# Sheet1.net
KiCad netlist of a schematic drawn in Altium Designer
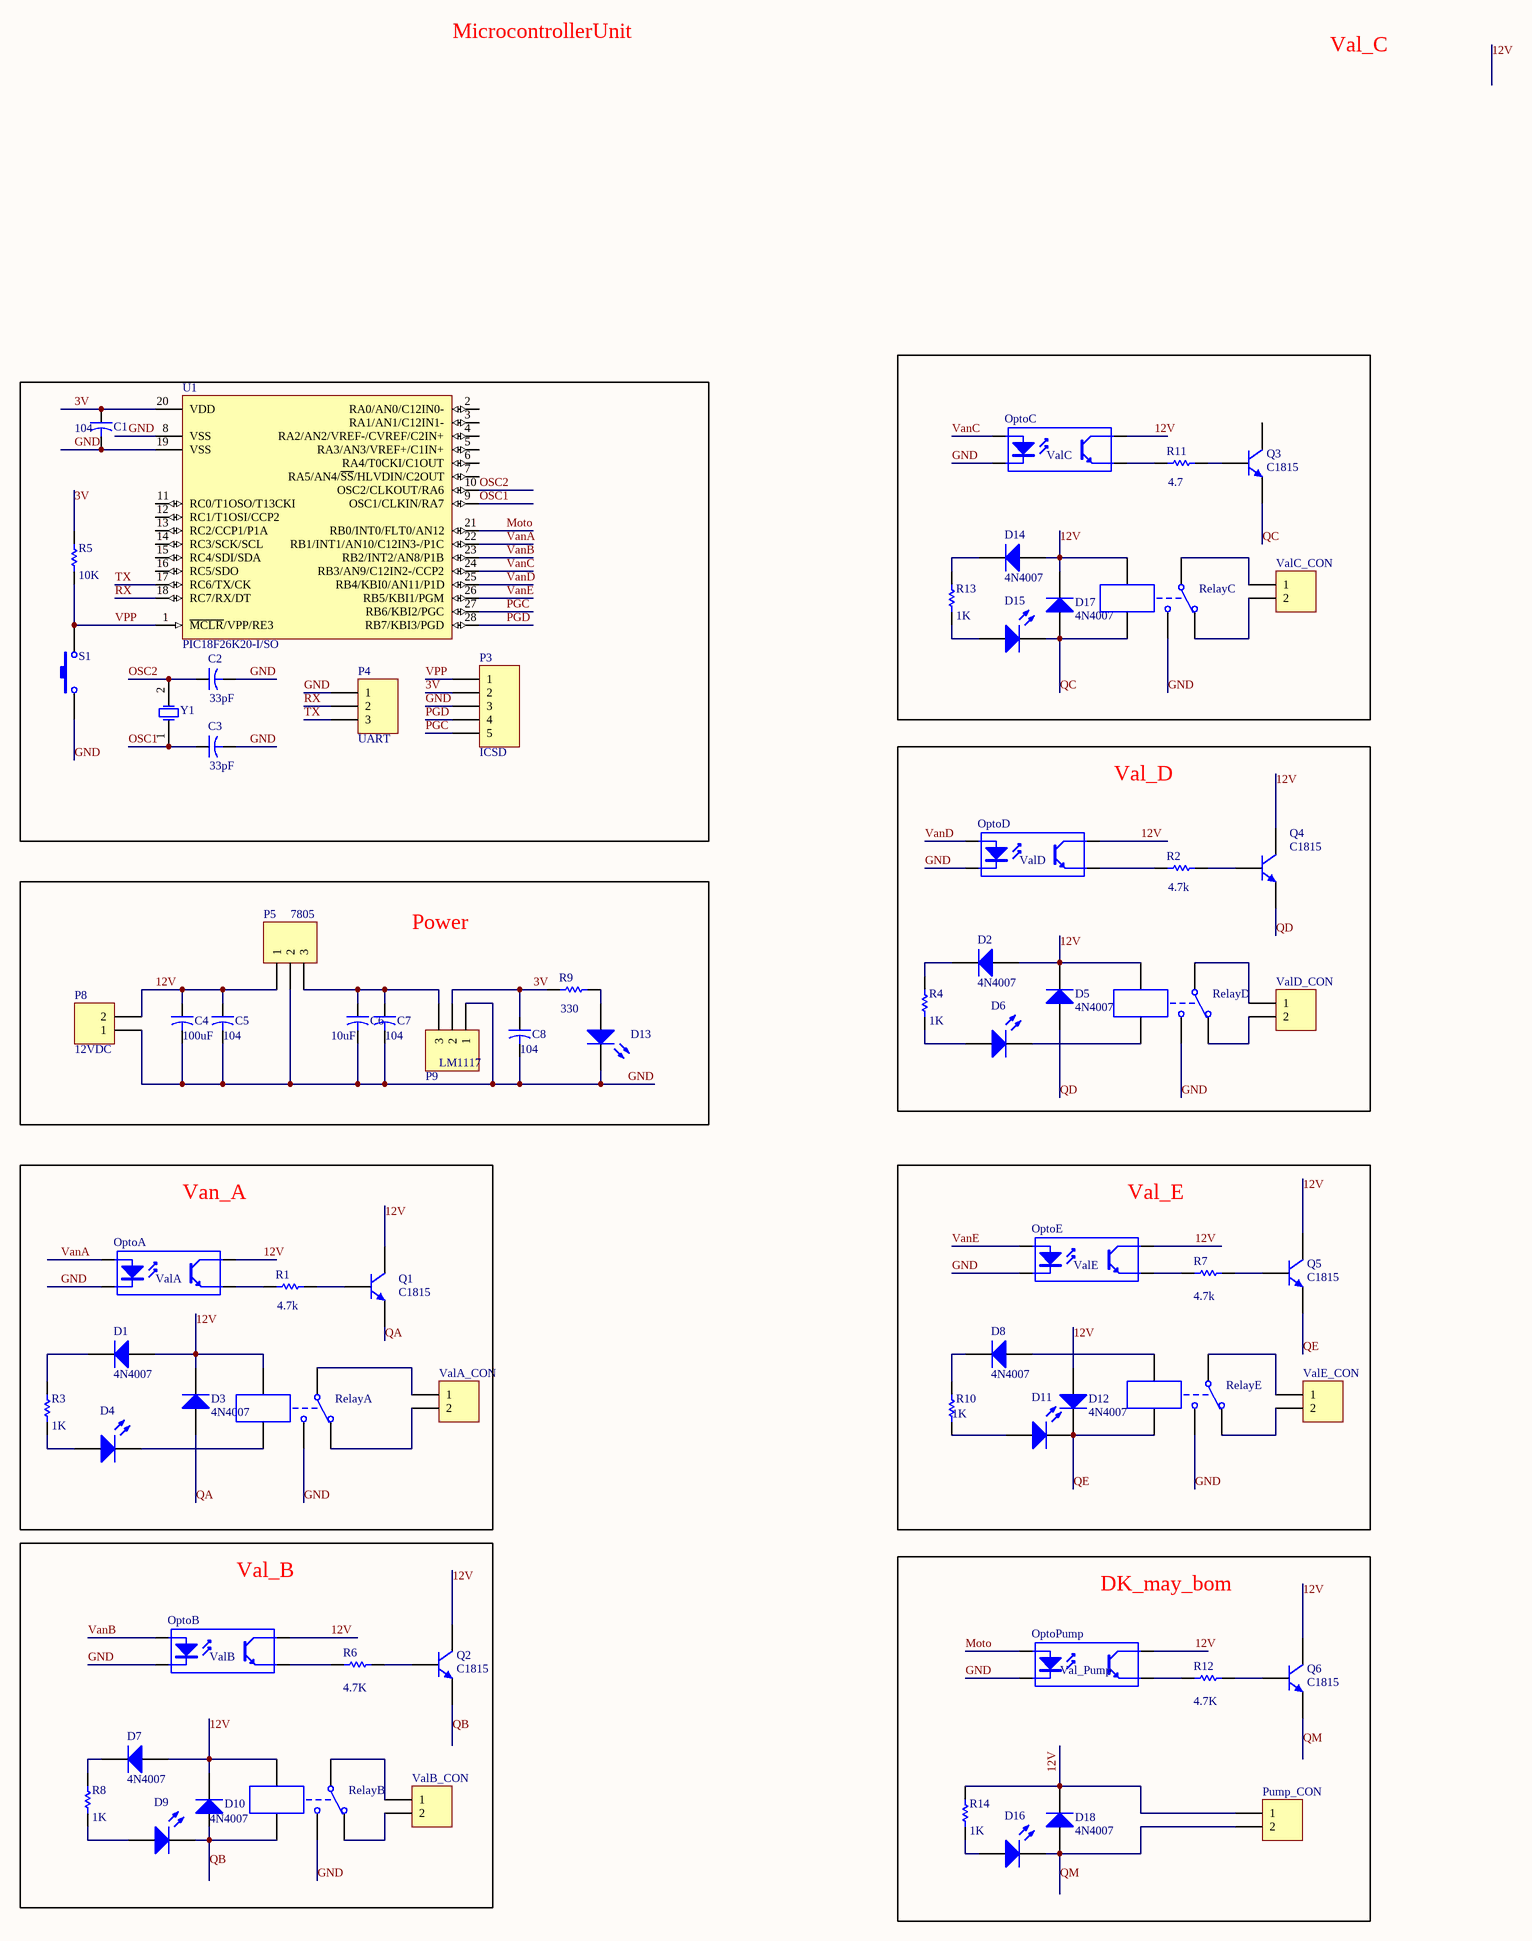
[diagram p0: Sheet1.SchDoc]

(export (version "E")
  (design (tool "Eeschema 10.0.6"))
  (components
    (comp (ref "C1")
      (value "104")
      (footprint "CN1")
      (description "Capacitor")
      (fields (field (name "Comment") "Cap2") (field (name "PUBLISHER") "Altium Limited"))
      (libsource (lib "Miscellaneous Devices") (part "Cap2"))
    )
    (comp (ref "C2")
      (value "33pF")
      (footprint "CN1")
      (description "Capacitor")
      (fields (field (name "Comment") "Cap2") (field (name "PUBLISHER") "Altium Limited"))
      (libsource (lib "Miscellaneous Devices") (part "Cap2"))
    )
    (comp (ref "C3")
      (value "33pF")
      (footprint "CN1")
      (description "Capacitor")
      (fields (field (name "Comment") "Cap2") (field (name "PUBLISHER") "Altium Limited"))
      (libsource (lib "Miscellaneous Devices") (part "Cap2"))
    )
    (comp (ref "C4")
      (value "100uF")
      (footprint "CP1.5/2.5")
      (description "Capacitor")
      (fields (field (name "Comment") "Cap2") (field (name "PUBLISHER") "Altium Limited"))
      (libsource (lib "Miscellaneous Devices") (part "Cap2"))
    )
    (comp (ref "C5")
      (value "104")
      (footprint "CN1")
      (description "Capacitor")
      (fields (field (name "Comment") "Cap2") (field (name "PUBLISHER") "Altium Limited"))
      (libsource (lib "Miscellaneous Devices") (part "Cap2"))
    )
    (comp (ref "C6")
      (value "10uF")
      (footprint "CP1/2")
      (description "Capacitor")
      (fields (field (name "Comment") "Cap2") (field (name "PUBLISHER") "Altium Limited"))
      (libsource (lib "Miscellaneous Devices") (part "Cap2"))
    )
    (comp (ref "C7")
      (value "104")
      (footprint "CN1")
      (description "Capacitor")
      (fields (field (name "Comment") "Cap2") (field (name "PUBLISHER") "Altium Limited"))
      (libsource (lib "Miscellaneous Devices") (part "Cap2"))
    )
    (comp (ref "C8")
      (value "104")
      (footprint "CN1")
      (description "Capacitor")
      (fields (field (name "Comment") "Cap2") (field (name "PUBLISHER") "Altium Limited"))
      (libsource (lib "Miscellaneous Devices") (part "Cap2"))
    )
    (comp (ref "D1")
      (value "4N4007")
      (footprint "D2A")
      (description "1 Amp General Purpose Rectifier")
      (fields (field (name "PUBLISHER") "Altium Limited"))
      (libsource (lib "Miscellaneous Devices") (part "Diode 1N4007"))
    )
    (comp (ref "D2")
      (value "4N4007")
      (footprint "D2A")
      (description "1 Amp General Purpose Rectifier")
      (fields (field (name "PUBLISHER") "Altium Limited"))
      (libsource (lib "Miscellaneous Devices") (part "Diode 1N4007"))
    )
    (comp (ref "D3")
      (value "4N4007")
      (footprint "D2A")
      (description "1 Amp General Purpose Rectifier")
      (fields (field (name "PUBLISHER") "Altium Limited"))
      (libsource (lib "Miscellaneous Devices") (part "Diode 1N4007"))
    )
    (comp (ref "D4")
      (value "LED1")
      (footprint "LED-5TRED")
      (description "Typical RED GaAs LED")
      (fields (field (name "PUBLISHER") "Altium Limited"))
      (libsource (lib "Miscellaneous Devices") (part "LED1"))
    )
    (comp (ref "D5")
      (value "4N4007")
      (footprint "D2A")
      (description "1 Amp General Purpose Rectifier")
      (fields (field (name "PUBLISHER") "Altium Limited"))
      (libsource (lib "Miscellaneous Devices") (part "Diode 1N4007"))
    )
    (comp (ref "D6")
      (value "LED1")
      (footprint "LED-5TRED")
      (description "Typical RED GaAs LED")
      (fields (field (name "PUBLISHER") "Altium Limited"))
      (libsource (lib "Miscellaneous Devices") (part "LED1"))
    )
    (comp (ref "D7")
      (value "4N4007")
      (footprint "D2A")
      (description "1 Amp General Purpose Rectifier")
      (fields (field (name "PUBLISHER") "Altium Limited"))
      (libsource (lib "Miscellaneous Devices") (part "Diode 1N4007"))
    )
    (comp (ref "D8")
      (value "4N4007")
      (footprint "D2A")
      (description "1 Amp General Purpose Rectifier")
      (fields (field (name "PUBLISHER") "Altium Limited"))
      (libsource (lib "Miscellaneous Devices") (part "Diode 1N4007"))
    )
    (comp (ref "D9")
      (value "LED1")
      (footprint "LED-5TRED")
      (description "Typical RED GaAs LED")
      (fields (field (name "PUBLISHER") "Altium Limited"))
      (libsource (lib "Miscellaneous Devices") (part "LED1"))
    )
    (comp (ref "D10")
      (value "4N4007")
      (footprint "D2A")
      (description "1 Amp General Purpose Rectifier")
      (fields (field (name "PUBLISHER") "Altium Limited"))
      (libsource (lib "Miscellaneous Devices") (part "Diode 1N4007"))
    )
    (comp (ref "D11")
      (value "LED1")
      (footprint "LED-5TRED")
      (description "Typical RED GaAs LED")
      (fields (field (name "PUBLISHER") "Altium Limited"))
      (libsource (lib "Miscellaneous Devices") (part "LED1"))
    )
    (comp (ref "D12")
      (value "4N4007")
      (footprint "D2A")
      (description "1 Amp General Purpose Rectifier")
      (fields (field (name "PUBLISHER") "Altium Limited"))
      (libsource (lib "Miscellaneous Devices") (part "Diode 1N4007"))
    )
    (comp (ref "D13")
      (value "LED1")
      (footprint "LED-5TRED")
      (description "Typical RED GaAs LED")
      (fields (field (name "PUBLISHER") "Altium Limited"))
      (libsource (lib "Miscellaneous Devices") (part "LED1"))
    )
    (comp (ref "D14")
      (value "4N4007")
      (footprint "D2A")
      (description "1 Amp General Purpose Rectifier")
      (fields (field (name "PUBLISHER") "Altium Limited"))
      (libsource (lib "Miscellaneous Devices") (part "Diode 1N4007"))
    )
    (comp (ref "D15")
      (value "LED1")
      (footprint "LED-5TRED")
      (description "Typical RED GaAs LED")
      (fields (field (name "PUBLISHER") "Altium Limited"))
      (libsource (lib "Miscellaneous Devices") (part "LED1"))
    )
    (comp (ref "D16")
      (value "LED1")
      (footprint "LED-5TRED")
      (description "Typical RED GaAs LED")
      (fields (field (name "PUBLISHER") "Altium Limited"))
      (libsource (lib "Miscellaneous Devices") (part "LED1"))
    )
    (comp (ref "D17")
      (value "4N4007")
      (footprint "D2A")
      (description "1 Amp General Purpose Rectifier")
      (fields (field (name "PUBLISHER") "Altium Limited"))
      (libsource (lib "Miscellaneous Devices") (part "Diode 1N4007"))
    )
    (comp (ref "D18")
      (value "4N4007")
      (footprint "D2A")
      (description "1 Amp General Purpose Rectifier")
      (fields (field (name "PUBLISHER") "Altium Limited"))
      (libsource (lib "Miscellaneous Devices") (part "Diode 1N4007"))
    )
    (comp (ref "OptoA")
      (value "ValA")
      (footprint "DIP4/W0.3")
      (description "4-Pin Phototransistor Optocoupler")
      (fields (field (name "PUBLISHER") "Altium Limited"))
      (libsource (lib "Miscellaneous Devices") (part "Optoisolator1"))
    )
    (comp (ref "OptoB")
      (value "ValB")
      (footprint "DIP4/W0.3")
      (description "4-Pin Phototransistor Optocoupler")
      (fields (field (name "PUBLISHER") "Altium Limited"))
      (libsource (lib "Miscellaneous Devices") (part "Optoisolator1"))
    )
    (comp (ref "OptoC")
      (value "ValC")
      (footprint "DIP4/W0.3")
      (description "4-Pin Phototransistor Optocoupler")
      (fields (field (name "PUBLISHER") "Altium Limited"))
      (libsource (lib "Miscellaneous Devices") (part "Optoisolator1"))
    )
    (comp (ref "OptoD")
      (value "ValD")
      (footprint "DIP4/W0.3")
      (description "4-Pin Phototransistor Optocoupler")
      (fields (field (name "PUBLISHER") "Altium Limited"))
      (libsource (lib "Miscellaneous Devices") (part "Optoisolator1"))
    )
    (comp (ref "OptoE")
      (value "ValE")
      (footprint "DIP4/W0.3")
      (description "4-Pin Phototransistor Optocoupler")
      (fields (field (name "PUBLISHER") "Altium Limited"))
      (libsource (lib "Miscellaneous Devices") (part "Optoisolator1"))
    )
    (comp (ref "OptoPump")
      (value "Val_Pump")
      (footprint "DIP4/W0.3")
      (description "4-Pin Phototransistor Optocoupler")
      (fields (field (name "PUBLISHER") "Altium Limited"))
      (libsource (lib "Miscellaneous Devices") (part "Optoisolator1"))
    )
    (comp (ref "P3")
      (value "ICSD")
      (footprint "JP5")
      (description "Header, 5-Pin, Right Angle")
      (fields (field (name "PUBLISHER") "Altium Limited"))
      (libsource (lib "Miscellaneous Connectors") (part "Header 5H"))
    )
    (comp (ref "P4")
      (value "UART")
      (footprint "JP3")
      (description "Header, 3-Pin, Right Angle")
      (fields (field (name "PUBLISHER") "Altium Limited"))
      (libsource (lib "Miscellaneous Connectors") (part "Header 3H"))
    )
    (comp (ref "P5")
      (value "7805")
      (footprint "JP3")
      (description "Header, 3-Pin, Right Angle")
      (fields (field (name "PUBLISHER") "Altium Limited"))
      (libsource (lib "") (part "Header 3H_2"))
    )
    (comp (ref "P8")
      (value "12VDC")
      (footprint "DC-IN")
      (description "Header, 2-Pin")
      (fields (field (name "PUBLISHER") "Altium Limited"))
      (libsource (lib "") (part "Header 2_1"))
    )
    (comp (ref "P9")
      (value "LM1117")
      (footprint "JP3")
      (description "Header, 3-Pin, Right Angle")
      (fields (field (name "PUBLISHER") "Altium Limited"))
      (libsource (lib "") (part "Header 3H_1"))
    )
    (comp (ref "Pump_CON")
      (value "Header 2")
      (footprint "CON2")
      (description "Header, 2-Pin")
      (fields (field (name "PUBLISHER") "Altium Limited"))
      (libsource (lib "Miscellaneous Connectors") (part "Header 2"))
    )
    (comp (ref "Q1")
      (value "C1815")
      (footprint "QTO-92")
      (description "NPN General Purpose Amplifier")
      (fields (field (name "PUBLISHER") "Altium Limited"))
      (libsource (lib "Miscellaneous Devices") (part "2N3904"))
    )
    (comp (ref "Q2")
      (value "C1815")
      (footprint "QTO-92")
      (description "NPN General Purpose Amplifier")
      (fields (field (name "PUBLISHER") "Altium Limited"))
      (libsource (lib "Miscellaneous Devices") (part "2N3904"))
    )
    (comp (ref "Q3")
      (value "C1815")
      (footprint "QTO-92")
      (description "NPN General Purpose Amplifier")
      (fields (field (name "PUBLISHER") "Altium Limited"))
      (libsource (lib "Miscellaneous Devices") (part "2N3904"))
    )
    (comp (ref "Q4")
      (value "C1815")
      (footprint "QTO-92")
      (description "NPN General Purpose Amplifier")
      (fields (field (name "PUBLISHER") "Altium Limited"))
      (libsource (lib "Miscellaneous Devices") (part "2N3904"))
    )
    (comp (ref "Q5")
      (value "C1815")
      (footprint "QTO-92")
      (description "NPN General Purpose Amplifier")
      (fields (field (name "PUBLISHER") "Altium Limited"))
      (libsource (lib "Miscellaneous Devices") (part "2N3904"))
    )
    (comp (ref "Q6")
      (value "C1815")
      (footprint "QTO-92")
      (description "NPN General Purpose Amplifier")
      (fields (field (name "PUBLISHER") "Altium Limited"))
      (libsource (lib "Miscellaneous Devices") (part "2N3904"))
    )
    (comp (ref "R1")
      (value "4.7k")
      (footprint "R1/4W")
      (description "Resistor")
      (fields (field (name "Comment") "Res1") (field (name "PUBLISHER") "Altium Limited"))
      (libsource (lib "Miscellaneous Devices") (part "Res1"))
    )
    (comp (ref "R2")
      (value "4.7k")
      (footprint "R1/4W")
      (description "Resistor")
      (fields (field (name "PUBLISHER") "Altium Limited"))
      (libsource (lib "Miscellaneous Devices") (part "Res1"))
    )
    (comp (ref "R3")
      (value "1K")
      (footprint "R1/4W")
      (description "Resistor")
      (fields (field (name "Comment") "Res1") (field (name "PUBLISHER") "Altium Limited"))
      (libsource (lib "Miscellaneous Devices") (part "Res1"))
    )
    (comp (ref "R4")
      (value "1K")
      (footprint "R1/4W")
      (description "Resistor")
      (fields (field (name "Comment") "Res1") (field (name "PUBLISHER") "Altium Limited"))
      (libsource (lib "Miscellaneous Devices") (part "Res1"))
    )
    (comp (ref "R5")
      (value "10K")
      (footprint "R1/4W")
      (description "Resistor")
      (fields (field (name "Comment") "Res1") (field (name "PUBLISHER") "Altium Limited"))
      (libsource (lib "Miscellaneous Devices") (part "Res1"))
    )
    (comp (ref "R6")
      (value "4.7K")
      (footprint "R1/4W")
      (description "Resistor")
      (fields (field (name "Comment") "Res1") (field (name "PUBLISHER") "Altium Limited"))
      (libsource (lib "Miscellaneous Devices") (part "Res1"))
    )
    (comp (ref "R7")
      (value "4.7k")
      (footprint "R1/4W")
      (description "Resistor")
      (fields (field (name "Comment") "Res1") (field (name "PUBLISHER") "Altium Limited"))
      (libsource (lib "Miscellaneous Devices") (part "Res1"))
    )
    (comp (ref "R8")
      (value "1K")
      (footprint "R1/4W")
      (description "Resistor")
      (fields (field (name "Comment") "Res1") (field (name "PUBLISHER") "Altium Limited"))
      (libsource (lib "Miscellaneous Devices") (part "Res1"))
    )
    (comp (ref "R9")
      (value "330")
      (footprint "R1/4W")
      (description "Resistor")
      (fields (field (name "Comment") "Res1") (field (name "PUBLISHER") "Altium Limited"))
      (libsource (lib "Miscellaneous Devices") (part "Res1"))
    )
    (comp (ref "R10")
      (value "1K")
      (footprint "R1/4W")
      (description "Resistor")
      (fields (field (name "Comment") "Res1") (field (name "PUBLISHER") "Altium Limited"))
      (libsource (lib "Miscellaneous Devices") (part "Res1"))
    )
    (comp (ref "R11")
      (value "4.7")
      (footprint "R1/4W")
      (description "Resistor")
      (fields (field (name "Comment") "Res1") (field (name "PUBLISHER") "Altium Limited"))
      (libsource (lib "Miscellaneous Devices") (part "Res1"))
    )
    (comp (ref "R12")
      (value "4.7K")
      (footprint "R1/4W")
      (description "Resistor")
      (fields (field (name "Comment") "Res1") (field (name "PUBLISHER") "Altium Limited"))
      (libsource (lib "Miscellaneous Devices") (part "Res1"))
    )
    (comp (ref "R13")
      (value "1K")
      (footprint "R1/4W")
      (description "Resistor")
      (fields (field (name "Comment") "Res1") (field (name "PUBLISHER") "Altium Limited"))
      (libsource (lib "Miscellaneous Devices") (part "Res1"))
    )
    (comp (ref "R14")
      (value "1K")
      (footprint "R1/4W")
      (description "Resistor")
      (fields (field (name "Comment") "Res1") (field (name "PUBLISHER") "Altium Limited"))
      (libsource (lib "Miscellaneous Devices") (part "Res1"))
    )
    (comp (ref "RelayA")
      (value "Relay-SPDT")
      (footprint "RL_SPDT_10A")
      (description "Single-Pole Dual-Throw Relay")
      (fields (field (name "PUBLISHER") "Altium Limited"))
      (libsource (lib "Miscellaneous Devices") (part "Relay-SPDT"))
    )
    (comp (ref "RelayB")
      (value "Relay-SPDT")
      (footprint "RL_SPDT_10A")
      (description "Single-Pole Dual-Throw Relay")
      (fields (field (name "PUBLISHER") "Altium Limited"))
      (libsource (lib "Miscellaneous Devices") (part "Relay-SPDT"))
    )
    (comp (ref "RelayC")
      (value "Relay-SPDT")
      (footprint "RL_SPDT_10A")
      (description "Single-Pole Dual-Throw Relay")
      (fields (field (name "PUBLISHER") "Altium Limited"))
      (libsource (lib "Miscellaneous Devices") (part "Relay-SPDT"))
    )
    (comp (ref "RelayD")
      (value "Relay-SPDT")
      (footprint "RL_SPDT_10A")
      (description "Single-Pole Dual-Throw Relay")
      (fields (field (name "PUBLISHER") "Altium Limited"))
      (libsource (lib "Miscellaneous Devices") (part "Relay-SPDT"))
    )
    (comp (ref "RelayE")
      (value "Relay-SPDT")
      (footprint "RL_SPDT_10A")
      (description "Single-Pole Dual-Throw Relay")
      (fields (field (name "PUBLISHER") "Altium Limited"))
      (libsource (lib "Miscellaneous Devices") (part "Relay-SPDT"))
    )
    (comp (ref "S1")
      (value "SW-PB")
      (footprint "SW2")
      (description "Switch")
      (fields (field (name "PUBLISHER") "Altium Limited"))
      (libsource (lib "Miscellaneous Devices") (part "SW-PB"))
    )
    (comp (ref "U1")
      (value "PIC18F26K20-I/SO")
      (footprint "SOP_28M_127")
      (fields (field (name "PUBLISHER") "Altium Limited"))
      (libsource (lib "Microchip Microcontroller 8-Bit PIC18") (part "PIC18F26K20-I/SO"))
    )
    (comp (ref "ValA_CON")
      (value "Header 2")
      (footprint "CON2")
      (description "Header, 2-Pin")
      (fields (field (name "PUBLISHER") "Altium Limited"))
      (libsource (lib "Miscellaneous Connectors") (part "Header 2"))
    )
    (comp (ref "ValB_CON")
      (value "Header 2")
      (footprint "CON2")
      (description "Header, 2-Pin")
      (fields (field (name "PUBLISHER") "Altium Limited"))
      (libsource (lib "Miscellaneous Connectors") (part "Header 2"))
    )
    (comp (ref "ValC_CON")
      (value "Header 2")
      (footprint "CON2")
      (description "Header, 2-Pin")
      (fields (field (name "PUBLISHER") "Altium Limited"))
      (libsource (lib "Miscellaneous Connectors") (part "Header 2"))
    )
    (comp (ref "ValD_CON")
      (value "Header 2")
      (footprint "CON2")
      (description "Header, 2-Pin")
      (fields (field (name "PUBLISHER") "Altium Limited"))
      (libsource (lib "Miscellaneous Connectors") (part "Header 2"))
    )
    (comp (ref "ValE_CON")
      (value "Header 2")
      (footprint "CON2")
      (description "Header, 2-Pin")
      (fields (field (name "PUBLISHER") "Altium Limited"))
      (libsource (lib "Miscellaneous Connectors") (part "Header 2"))
    )
    (comp (ref "Y1")
      (value "8Mhz")
      (footprint "XT2")
      (description "Crystal Oscillator")
      (fields (field (name "PUBLISHER") "Altium Limited"))
      (libsource (lib "Miscellaneous Devices") (part "XTAL"))
    )
  )
  (nets
    (net (code "1") (name "/3V") (class "Default")
      (node (ref "C1") (pin "1") (pinfunction "1_1") (pintype "passive"))
      (node (ref "C8") (pin "1") (pinfunction "1_1") (pintype "passive"))
      (node (ref "P3") (pin "2") (pinfunction "2_2") (pintype "passive"))
      (node (ref "P9") (pin "2") (pinfunction "2_2") (pintype "passive"))
      (node (ref "R5") (pin "2") (pinfunction "2_2") (pintype "passive"))
      (node (ref "R9") (pin "1") (pinfunction "1_1") (pintype "passive"))
      (node (ref "U1") (pin "20") (pinfunction "VDD_20") (pintype "power_in"))
    )
    (net (code "2") (name "/12V") (class "Default")
      (node (ref "C4") (pin "1") (pinfunction "1_1") (pintype "passive"))
      (node (ref "C5") (pin "1") (pinfunction "1_1") (pintype "passive"))
      (node (ref "D1") (pin "1") (pinfunction "A_1") (pintype "passive"))
      (node (ref "D10") (pin "2") (pinfunction "K_2") (pintype "passive"))
      (node (ref "D12") (pin "1") (pinfunction "A_1") (pintype "passive"))
      (node (ref "D14") (pin "1") (pinfunction "A_1") (pintype "passive"))
      (node (ref "D17") (pin "2") (pinfunction "K_2") (pintype "passive"))
      (node (ref "D18") (pin "2") (pinfunction "K_2") (pintype "passive"))
      (node (ref "D2") (pin "1") (pinfunction "A_1") (pintype "passive"))
      (node (ref "D3") (pin "2") (pinfunction "K_2") (pintype "passive"))
      (node (ref "D5") (pin "2") (pinfunction "K_2") (pintype "passive"))
      (node (ref "D7") (pin "1") (pinfunction "A_1") (pintype "passive"))
      (node (ref "OptoA") (pin "4") (pinfunction "C_4") (pintype "passive"))
      (node (ref "OptoB") (pin "4") (pinfunction "C_4") (pintype "passive"))
      (node (ref "OptoC") (pin "4") (pinfunction "C_4") (pintype "passive"))
      (node (ref "OptoD") (pin "4") (pinfunction "C_4") (pintype "passive"))
      (node (ref "OptoE") (pin "4") (pinfunction "C_4") (pintype "passive"))
      (node (ref "OptoPump") (pin "4") (pinfunction "C_4") (pintype "passive"))
      (node (ref "P5") (pin "1") (pinfunction "1_1") (pintype "passive"))
      (node (ref "P8") (pin "2") (pinfunction "2_2") (pintype "passive"))
      (node (ref "Pump_CON") (pin "1") (pinfunction "1_1") (pintype "passive"))
      (node (ref "Q1") (pin "3") (pinfunction "C_3") (pintype "passive"))
      (node (ref "Q2") (pin "3") (pinfunction "C_3") (pintype "passive"))
      (node (ref "Q4") (pin "3") (pinfunction "C_3") (pintype "passive"))
      (node (ref "Q5") (pin "3") (pinfunction "C_3") (pintype "passive"))
      (node (ref "Q6") (pin "3") (pinfunction "C_3") (pintype "passive"))
      (node (ref "R14") (pin "1") (pinfunction "1_1") (pintype "passive"))
      (node (ref "RelayA") (pin "4") (pinfunction "4_4") (pintype "passive"))
      (node (ref "RelayB") (pin "4") (pinfunction "4_4") (pintype "passive"))
      (node (ref "RelayC") (pin "4") (pinfunction "4_4") (pintype "passive"))
      (node (ref "RelayD") (pin "4") (pinfunction "4_4") (pintype "passive"))
    )
    (net (code "3") (name "/GND") (class "Default")
      (node (ref "C1") (pin "2") (pinfunction "2_2") (pintype "passive"))
      (node (ref "C2") (pin "2") (pinfunction "2_2") (pintype "passive"))
      (node (ref "C3") (pin "2") (pinfunction "2_2") (pintype "passive"))
      (node (ref "C4") (pin "2") (pinfunction "2_2") (pintype "passive"))
      (node (ref "C5") (pin "2") (pinfunction "2_2") (pintype "passive"))
      (node (ref "C6") (pin "2") (pinfunction "2_2") (pintype "passive"))
      (node (ref "C7") (pin "2") (pinfunction "2_2") (pintype "passive"))
      (node (ref "C8") (pin "2") (pinfunction "2_2") (pintype "passive"))
      (node (ref "D13") (pin "2") (pinfunction "K_2") (pintype "passive"))
      (node (ref "OptoA") (pin "2") (pinfunction "K_2") (pintype "passive"))
      (node (ref "OptoB") (pin "2") (pinfunction "K_2") (pintype "passive"))
      (node (ref "OptoC") (pin "2") (pinfunction "K_2") (pintype "passive"))
      (node (ref "OptoD") (pin "2") (pinfunction "K_2") (pintype "passive"))
      (node (ref "OptoE") (pin "2") (pinfunction "K_2") (pintype "passive"))
      (node (ref "OptoPump") (pin "2") (pinfunction "K_2") (pintype "passive"))
      (node (ref "P3") (pin "3") (pinfunction "3_3") (pintype "passive"))
      (node (ref "P4") (pin "1") (pinfunction "1_1") (pintype "passive"))
      (node (ref "P5") (pin "2") (pinfunction "2_2") (pintype "passive"))
      (node (ref "P8") (pin "1") (pinfunction "1_1") (pintype "passive"))
      (node (ref "P9") (pin "1") (pinfunction "1_1") (pintype "passive"))
      (node (ref "RelayA") (pin "3") (pinfunction "3_3") (pintype "passive"))
      (node (ref "RelayB") (pin "3") (pinfunction "3_3") (pintype "passive"))
      (node (ref "RelayC") (pin "3") (pinfunction "3_3") (pintype "passive"))
      (node (ref "RelayD") (pin "3") (pinfunction "3_3") (pintype "passive"))
      (node (ref "RelayE") (pin "3") (pinfunction "3_3") (pintype "passive"))
      (node (ref "S1") (pin "1") (pinfunction "1_1") (pintype "passive"))
      (node (ref "U1") (pin "19") (pinfunction "VSS_19") (pintype "power_in"))
      (node (ref "U1") (pin "8") (pinfunction "VSS_8") (pintype "power_in"))
    )
    (net (code "4") (name "/Moto") (class "Default")
      (node (ref "OptoPump") (pin "1") (pinfunction "A_1") (pintype "passive"))
      (node (ref "U1") (pin "21") (pinfunction "RB0/INT0/FLT0/AN12_21") (pintype "bidirectional"))
    )
    (net (code "5") (name "/OSC1") (class "Default")
      (node (ref "C3") (pin "1") (pinfunction "1_1") (pintype "passive"))
      (node (ref "U1") (pin "9") (pinfunction "OSC1/CLKIN/RA7_9") (pintype "bidirectional"))
      (node (ref "Y1") (pin "1") (pinfunction "OSC1_1") (pintype "passive"))
    )
    (net (code "6") (name "/OSC2") (class "Default")
      (node (ref "C2") (pin "1") (pinfunction "1_1") (pintype "passive"))
      (node (ref "U1") (pin "10") (pinfunction "OSC2/CLKOUT/RA6_10") (pintype "bidirectional"))
      (node (ref "Y1") (pin "2") (pinfunction "OSC2_2") (pintype "passive"))
    )
    (net (code "7") (name "/PGC") (class "Default")
      (node (ref "P3") (pin "5") (pinfunction "5_5") (pintype "passive"))
      (node (ref "U1") (pin "27") (pinfunction "RB6/KBI2/PGC_27") (pintype "bidirectional"))
    )
    (net (code "8") (name "/PGD") (class "Default")
      (node (ref "P3") (pin "4") (pinfunction "4_4") (pintype "passive"))
      (node (ref "U1") (pin "28") (pinfunction "RB7/KBI3/PGD_28") (pintype "bidirectional"))
    )
    (net (code "9") (name "/QA") (class "Default")
      (node (ref "D3") (pin "1") (pinfunction "A_1") (pintype "passive"))
      (node (ref "Q1") (pin "1") (pinfunction "E_1") (pintype "passive"))
    )
    (net (code "10") (name "/QB") (class "Default")
      (node (ref "D10") (pin "1") (pinfunction "A_1") (pintype "passive"))
      (node (ref "D9") (pin "2") (pinfunction "K_2") (pintype "passive"))
      (node (ref "Q2") (pin "1") (pinfunction "E_1") (pintype "passive"))
      (node (ref "RelayB") (pin "5") (pinfunction "5_5") (pintype "passive"))
    )
    (net (code "11") (name "/QC") (class "Default")
      (node (ref "D15") (pin "2") (pinfunction "K_2") (pintype "passive"))
      (node (ref "D17") (pin "1") (pinfunction "A_1") (pintype "passive"))
      (node (ref "Q3") (pin "1") (pinfunction "E_1") (pintype "passive"))
      (node (ref "RelayC") (pin "5") (pinfunction "5_5") (pintype "passive"))
    )
    (net (code "12") (name "/QD") (class "Default")
      (node (ref "D5") (pin "1") (pinfunction "A_1") (pintype "passive"))
      (node (ref "Q4") (pin "1") (pinfunction "E_1") (pintype "passive"))
    )
    (net (code "13") (name "/QE") (class "Default")
      (node (ref "D11") (pin "2") (pinfunction "K_2") (pintype "passive"))
      (node (ref "D12") (pin "2") (pinfunction "K_2") (pintype "passive"))
      (node (ref "Q5") (pin "1") (pinfunction "E_1") (pintype "passive"))
      (node (ref "RelayE") (pin "5") (pinfunction "5_5") (pintype "passive"))
    )
    (net (code "14") (name "/QM") (class "Default")
      (node (ref "D16") (pin "2") (pinfunction "K_2") (pintype "passive"))
      (node (ref "D18") (pin "1") (pinfunction "A_1") (pintype "passive"))
      (node (ref "Pump_CON") (pin "2") (pinfunction "2_2") (pintype "passive"))
      (node (ref "Q6") (pin "1") (pinfunction "E_1") (pintype "passive"))
    )
    (net (code "15") (name "/RX") (class "Default")
      (node (ref "P4") (pin "2") (pinfunction "2_2") (pintype "passive"))
      (node (ref "U1") (pin "18") (pinfunction "RC7/RX/DT_18") (pintype "bidirectional"))
    )
    (net (code "16") (name "/TX") (class "Default")
      (node (ref "P4") (pin "3") (pinfunction "3_3") (pintype "passive"))
      (node (ref "U1") (pin "17") (pinfunction "RC6/TX/CK_17") (pintype "bidirectional"))
    )
    (net (code "17") (name "/VPP") (class "Default")
      (node (ref "P3") (pin "1") (pinfunction "1_1") (pintype "passive"))
      (node (ref "R5") (pin "1") (pinfunction "1_1") (pintype "passive"))
      (node (ref "S1") (pin "2") (pinfunction "2_2") (pintype "passive"))
      (node (ref "U1") (pin "1") (pinfunction "~{MCLR}/VPP/RE3_1") (pintype "input"))
    )
    (net (code "18") (name "/VanA") (class "Default")
      (node (ref "OptoA") (pin "1") (pinfunction "A_1") (pintype "passive"))
      (node (ref "U1") (pin "22") (pinfunction "RB1/INT1/AN10/C12IN3-/P1C_22") (pintype "bidirectional"))
    )
    (net (code "19") (name "/VanB") (class "Default")
      (node (ref "OptoB") (pin "1") (pinfunction "A_1") (pintype "passive"))
      (node (ref "U1") (pin "23") (pinfunction "RB2/INT2/AN8/P1B_23") (pintype "bidirectional"))
    )
    (net (code "20") (name "/VanC") (class "Default")
      (node (ref "OptoC") (pin "1") (pinfunction "A_1") (pintype "passive"))
      (node (ref "U1") (pin "24") (pinfunction "RB3/AN9/C12IN2-/CCP2_24") (pintype "bidirectional"))
    )
    (net (code "21") (name "/VanD") (class "Default")
      (node (ref "OptoD") (pin "1") (pinfunction "A_1") (pintype "passive"))
      (node (ref "U1") (pin "25") (pinfunction "RB4/KBI0/AN11/P1D_25") (pintype "bidirectional"))
    )
    (net (code "22") (name "/VanE") (class "Default")
      (node (ref "OptoE") (pin "1") (pinfunction "A_1") (pintype "passive"))
      (node (ref "U1") (pin "26") (pinfunction "RB5/KBI1/PGM_26") (pintype "bidirectional"))
    )
    (net (code "23") (name "Net-(C6-Pad1)") (class "Default")
      (node (ref "C6") (pin "1") (pinfunction "1_1") (pintype "passive"))
      (node (ref "C7") (pin "1") (pinfunction "1_1") (pintype "passive"))
      (node (ref "P5") (pin "3") (pinfunction "3_3") (pintype "passive"))
      (node (ref "P9") (pin "3") (pinfunction "3_3") (pintype "passive"))
    )
    (net (code "24") (name "Net-(D1-K)") (class "Default")
      (node (ref "D1") (pin "2") (pinfunction "K_2") (pintype "passive"))
      (node (ref "R3") (pin "1") (pinfunction "1_1") (pintype "passive"))
    )
    (net (code "25") (name "Net-(D2-K)") (class "Default")
      (node (ref "D2") (pin "2") (pinfunction "K_2") (pintype "passive"))
      (node (ref "R4") (pin "1") (pinfunction "1_1") (pintype "passive"))
    )
    (net (code "26") (name "Net-(D4-A)") (class "Default")
      (node (ref "D4") (pin "1") (pinfunction "A_1") (pintype "passive"))
      (node (ref "R3") (pin "2") (pinfunction "2_2") (pintype "passive"))
    )
    (net (code "27") (name "Net-(D4-K)") (class "Default")
      (node (ref "D4") (pin "2") (pinfunction "K_2") (pintype "passive"))
      (node (ref "RelayA") (pin "5") (pinfunction "5_5") (pintype "passive"))
    )
    (net (code "28") (name "Net-(D6-A)") (class "Default")
      (node (ref "D6") (pin "1") (pinfunction "A_1") (pintype "passive"))
      (node (ref "R4") (pin "2") (pinfunction "2_2") (pintype "passive"))
    )
    (net (code "29") (name "Net-(D6-K)") (class "Default")
      (node (ref "D6") (pin "2") (pinfunction "K_2") (pintype "passive"))
      (node (ref "RelayD") (pin "5") (pinfunction "5_5") (pintype "passive"))
    )
    (net (code "30") (name "Net-(D7-K)") (class "Default")
      (node (ref "D7") (pin "2") (pinfunction "K_2") (pintype "passive"))
      (node (ref "R8") (pin "1") (pinfunction "1_1") (pintype "passive"))
    )
    (net (code "31") (name "Net-(D8-A)") (class "Default")
      (node (ref "D8") (pin "1") (pinfunction "A_1") (pintype "passive"))
      (node (ref "RelayE") (pin "4") (pinfunction "4_4") (pintype "passive"))
    )
    (net (code "32") (name "Net-(D8-K)") (class "Default")
      (node (ref "D8") (pin "2") (pinfunction "K_2") (pintype "passive"))
      (node (ref "R10") (pin "1") (pinfunction "1_1") (pintype "passive"))
    )
    (net (code "33") (name "Net-(D9-A)") (class "Default")
      (node (ref "D9") (pin "1") (pinfunction "A_1") (pintype "passive"))
      (node (ref "R8") (pin "2") (pinfunction "2_2") (pintype "passive"))
    )
    (net (code "34") (name "Net-(D11-A)") (class "Default")
      (node (ref "D11") (pin "1") (pinfunction "A_1") (pintype "passive"))
      (node (ref "R10") (pin "2") (pinfunction "2_2") (pintype "passive"))
    )
    (net (code "35") (name "Net-(D13-A)") (class "Default")
      (node (ref "D13") (pin "1") (pinfunction "A_1") (pintype "passive"))
      (node (ref "R9") (pin "2") (pinfunction "2_2") (pintype "passive"))
    )
    (net (code "36") (name "Net-(D14-K)") (class "Default")
      (node (ref "D14") (pin "2") (pinfunction "K_2") (pintype "passive"))
      (node (ref "R13") (pin "1") (pinfunction "1_1") (pintype "passive"))
    )
    (net (code "37") (name "Net-(D15-A)") (class "Default")
      (node (ref "D15") (pin "1") (pinfunction "A_1") (pintype "passive"))
      (node (ref "R13") (pin "2") (pinfunction "2_2") (pintype "passive"))
    )
    (net (code "38") (name "Net-(D16-A)") (class "Default")
      (node (ref "D16") (pin "1") (pinfunction "A_1") (pintype "passive"))
      (node (ref "R14") (pin "2") (pinfunction "2_2") (pintype "passive"))
    )
    (net (code "39") (name "Net-(OptoA-E)") (class "Default")
      (node (ref "OptoA") (pin "3") (pinfunction "E_3") (pintype "passive"))
      (node (ref "R1") (pin "1") (pinfunction "1_1") (pintype "passive"))
    )
    (net (code "40") (name "Net-(OptoB-E)") (class "Default")
      (node (ref "OptoB") (pin "3") (pinfunction "E_3") (pintype "passive"))
      (node (ref "R6") (pin "1") (pinfunction "1_1") (pintype "passive"))
    )
    (net (code "41") (name "Net-(OptoC-E)") (class "Default")
      (node (ref "OptoC") (pin "3") (pinfunction "E_3") (pintype "passive"))
      (node (ref "R11") (pin "1") (pinfunction "1_1") (pintype "passive"))
    )
    (net (code "42") (name "Net-(OptoD-E)") (class "Default")
      (node (ref "OptoD") (pin "3") (pinfunction "E_3") (pintype "passive"))
      (node (ref "R2") (pin "1") (pinfunction "1_1") (pintype "passive"))
    )
    (net (code "43") (name "Net-(OptoE-E)") (class "Default")
      (node (ref "OptoE") (pin "3") (pinfunction "E_3") (pintype "passive"))
      (node (ref "R7") (pin "1") (pinfunction "1_1") (pintype "passive"))
    )
    (net (code "44") (name "Net-(OptoPump-E)") (class "Default")
      (node (ref "OptoPump") (pin "3") (pinfunction "E_3") (pintype "passive"))
      (node (ref "R12") (pin "1") (pinfunction "1_1") (pintype "passive"))
    )
    (net (code "45") (name "Net-(Q1-B)") (class "Default")
      (node (ref "Q1") (pin "2") (pinfunction "B_2") (pintype "passive"))
      (node (ref "R1") (pin "2") (pinfunction "2_2") (pintype "passive"))
    )
    (net (code "46") (name "Net-(Q2-B)") (class "Default")
      (node (ref "Q2") (pin "2") (pinfunction "B_2") (pintype "passive"))
      (node (ref "R6") (pin "2") (pinfunction "2_2") (pintype "passive"))
    )
    (net (code "47") (name "Net-(Q3-B)") (class "Default")
      (node (ref "Q3") (pin "2") (pinfunction "B_2") (pintype "passive"))
      (node (ref "R11") (pin "2") (pinfunction "2_2") (pintype "passive"))
    )
    (net (code "48") (name "Net-(Q4-B)") (class "Default")
      (node (ref "Q4") (pin "2") (pinfunction "B_2") (pintype "passive"))
      (node (ref "R2") (pin "2") (pinfunction "2_2") (pintype "passive"))
    )
    (net (code "49") (name "Net-(Q5-B)") (class "Default")
      (node (ref "Q5") (pin "2") (pinfunction "B_2") (pintype "passive"))
      (node (ref "R7") (pin "2") (pinfunction "2_2") (pintype "passive"))
    )
    (net (code "50") (name "Net-(Q6-B)") (class "Default")
      (node (ref "Q6") (pin "2") (pinfunction "B_2") (pintype "passive"))
      (node (ref "R12") (pin "2") (pinfunction "2_2") (pintype "passive"))
    )
    (net (code "51") (name "Net-(RelayA-Pad1)") (class "Default")
      (node (ref "RelayA") (pin "1") (pinfunction "1_1") (pintype "passive"))
      (node (ref "ValA_CON") (pin "1") (pinfunction "1_1") (pintype "passive"))
    )
    (net (code "52") (name "Net-(RelayA-Pad2)") (class "Default")
      (node (ref "RelayA") (pin "2") (pinfunction "2_2") (pintype "passive"))
      (node (ref "ValA_CON") (pin "2") (pinfunction "2_2") (pintype "passive"))
    )
    (net (code "53") (name "Net-(RelayB-Pad1)") (class "Default")
      (node (ref "RelayB") (pin "1") (pinfunction "1_1") (pintype "passive"))
      (node (ref "ValB_CON") (pin "1") (pinfunction "1_1") (pintype "passive"))
    )
    (net (code "54") (name "Net-(RelayB-Pad2)") (class "Default")
      (node (ref "RelayB") (pin "2") (pinfunction "2_2") (pintype "passive"))
      (node (ref "ValB_CON") (pin "2") (pinfunction "2_2") (pintype "passive"))
    )
    (net (code "55") (name "Net-(RelayC-Pad1)") (class "Default")
      (node (ref "RelayC") (pin "1") (pinfunction "1_1") (pintype "passive"))
      (node (ref "ValC_CON") (pin "1") (pinfunction "1_1") (pintype "passive"))
    )
    (net (code "56") (name "Net-(RelayC-Pad2)") (class "Default")
      (node (ref "RelayC") (pin "2") (pinfunction "2_2") (pintype "passive"))
      (node (ref "ValC_CON") (pin "2") (pinfunction "2_2") (pintype "passive"))
    )
    (net (code "57") (name "Net-(RelayD-Pad1)") (class "Default")
      (node (ref "RelayD") (pin "1") (pinfunction "1_1") (pintype "passive"))
      (node (ref "ValD_CON") (pin "1") (pinfunction "1_1") (pintype "passive"))
    )
    (net (code "58") (name "Net-(RelayD-Pad2)") (class "Default")
      (node (ref "RelayD") (pin "2") (pinfunction "2_2") (pintype "passive"))
      (node (ref "ValD_CON") (pin "2") (pinfunction "2_2") (pintype "passive"))
    )
    (net (code "59") (name "Net-(RelayE-Pad1)") (class "Default")
      (node (ref "RelayE") (pin "1") (pinfunction "1_1") (pintype "passive"))
      (node (ref "ValE_CON") (pin "1") (pinfunction "1_1") (pintype "passive"))
    )
    (net (code "60") (name "Net-(RelayE-Pad2)") (class "Default")
      (node (ref "RelayE") (pin "2") (pinfunction "2_2") (pintype "passive"))
      (node (ref "ValE_CON") (pin "2") (pinfunction "2_2") (pintype "passive"))
    )
    (net (code "61") (name "unconnected-(Q3-C-Pad3)") (class "Default")
      (node (ref "Q3") (pin "3") (pinfunction "C_3") (pintype "passive"))
    )
    (net (code "62") (name "unconnected-(U1-RA0{slash}AN0{slash}C12IN0--Pad2)") (class "Default")
      (node (ref "U1") (pin "2") (pinfunction "RA0/AN0/C12IN0-_2") (pintype "bidirectional"))
    )
    (net (code "63") (name "unconnected-(U1-RA1{slash}AN1{slash}C12IN1--Pad3)") (class "Default")
      (node (ref "U1") (pin "3") (pinfunction "RA1/AN1/C12IN1-_3") (pintype "bidirectional"))
    )
    (net (code "64") (name "unconnected-(U1-RA2{slash}AN2{slash}VREF-{slash}CVREF{slash}C2IN+-Pad4)") (class "Default")
      (node (ref "U1") (pin "4") (pinfunction "RA2/AN2/VREF-/CVREF/C2IN+_4") (pintype "bidirectional"))
    )
    (net (code "65") (name "unconnected-(U1-RA3{slash}AN3{slash}VREF+{slash}C1IN+-Pad5)") (class "Default")
      (node (ref "U1") (pin "5") (pinfunction "RA3/AN3/VREF+/C1IN+_5") (pintype "bidirectional"))
    )
    (net (code "66") (name "unconnected-(U1-RA4{slash}T0CKI{slash}C1OUT-Pad6)") (class "Default")
      (node (ref "U1") (pin "6") (pinfunction "RA4/T0CKI/C1OUT_6") (pintype "bidirectional"))
    )
    (net (code "67") (name "unconnected-(U1-RA5{slash}AN4{slash}~{SS}{slash}HLVDIN{slash}C2OUT-Pad7)") (class "Default")
      (node (ref "U1") (pin "7") (pinfunction "RA5/AN4/~{SS}/HLVDIN/C2OUT_7") (pintype "bidirectional"))
    )
    (net (code "68") (name "unconnected-(U1-RC0{slash}T1OSO{slash}T13CKI-Pad11)") (class "Default")
      (node (ref "U1") (pin "11") (pinfunction "RC0/T1OSO/T13CKI_11") (pintype "bidirectional"))
    )
    (net (code "69") (name "unconnected-(U1-RC1{slash}T1OSI{slash}CCP2-Pad12)") (class "Default")
      (node (ref "U1") (pin "12") (pinfunction "RC1/T1OSI/CCP2_12") (pintype "bidirectional"))
    )
    (net (code "70") (name "unconnected-(U1-RC2{slash}CCP1{slash}P1A-Pad13)") (class "Default")
      (node (ref "U1") (pin "13") (pinfunction "RC2/CCP1/P1A_13") (pintype "bidirectional"))
    )
    (net (code "71") (name "unconnected-(U1-RC3{slash}SCK{slash}SCL-Pad14)") (class "Default")
      (node (ref "U1") (pin "14") (pinfunction "RC3/SCK/SCL_14") (pintype "bidirectional"))
    )
    (net (code "72") (name "unconnected-(U1-RC4{slash}SDI{slash}SDA-Pad15)") (class "Default")
      (node (ref "U1") (pin "15") (pinfunction "RC4/SDI/SDA_15") (pintype "bidirectional"))
    )
    (net (code "73") (name "unconnected-(U1-RC5{slash}SDO-Pad16)") (class "Default")
      (node (ref "U1") (pin "16") (pinfunction "RC5/SDO_16") (pintype "bidirectional"))
    )
  )
)
